# power-afe.net
KiCad netlist of a schematic drawn in Altium Designer
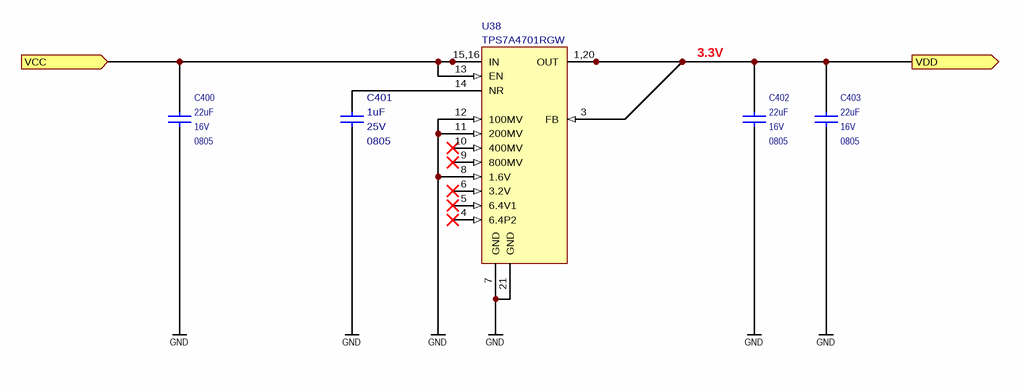
[diagram p0: power-afe.SchDoc]

(export (version "E")
  (design (tool "Eeschema 10.0.6"))
  (components
    (comp (ref "C400")
      (value "22uF")
      (footprint "generic:CAPC200X125X145L45N")
      (description "Ceramic Capacitor 22uF ±10% 16V X5R 0805")
      (fields
        (field (name "MANUFACTURER") "TDK")
        (field (name "VOLTAGE") "16V")
        (field (name "PACKAGE") "0805")
        (field (name "TOLERANCE") "±10%")
      )
      (libsource (lib "generic") (part "CAP 0603"))
    )
    (comp (ref "C401")
      (value "1uF")
      (footprint "CAPC200X125X145L45N")
      (description "Ceramic Capacitor 1uF ±10% 25V X7R 0805")
      (fields
        (field (name "MANUFACTURER") "Taiyo Yuden")
        (field (name "TOLERANCE") "±10%")
        (field (name "PACKAGE") "0805")
        (field (name "VOLTAGE") "25V")
      )
      (libsource (lib "capacitors") (part "CAP"))
    )
    (comp (ref "C402")
      (value "22uF")
      (footprint "generic:CAPC200X125X145L45N")
      (description "Ceramic Capacitor 22uF ±10% 16V X5R 0805")
      (fields
        (field (name "MANUFACTURER") "TDK")
        (field (name "VOLTAGE") "16V")
        (field (name "PACKAGE") "0805")
        (field (name "TOLERANCE") "±10%")
      )
      (libsource (lib "generic") (part "CAP 0603"))
    )
    (comp (ref "C403")
      (value "22uF")
      (footprint "generic:CAPC200X125X145L45N")
      (description "Ceramic Capacitor 22uF ±10% 16V X5R 0805")
      (fields
        (field (name "MANUFACTURER") "TDK")
        (field (name "VOLTAGE") "16V")
        (field (name "PACKAGE") "0805")
        (field (name "TOLERANCE") "±10%")
      )
      (libsource (lib "generic") (part "CAP 0603"))
    )
    (comp (ref "U38")
      (value "TPS7A4701RGW")
      (footprint "QFN65P500X500X100-21N")
      (description "Low-Dropout Linear Regulator 20-VQFN")
      (fields (field (name "MANUFACTURER") "Texas Instruments"))
      (libsource (lib "ti") (part "TPS7A4701RGW_1"))
    )
  )
  (nets
    (net (code "1") (name "/VCC") (class "Default")
      (node (ref "C400") (pin "2") (pinfunction "2_2") (pintype "passive"))
      (node (ref "U38") (pin "13") (pinfunction "EN_13") (pintype "input"))
      (node (ref "U38") (pin "15") (pinfunction "IN_15") (pintype "passive"))
      (node (ref "U38") (pin "16") (pinfunction "IN_16") (pintype "passive"))
    )
    (net (code "2") (name "/VDD") (class "Default")
      (node (ref "C402") (pin "2") (pinfunction "2_2") (pintype "passive"))
      (node (ref "C403") (pin "2") (pinfunction "2_2") (pintype "passive"))
      (node (ref "U38") (pin "1") (pinfunction "OUT_1") (pintype "passive"))
      (node (ref "U38") (pin "20") (pinfunction "OUT_20") (pintype "passive"))
      (node (ref "U38") (pin "3") (pinfunction "FB_3") (pintype "input"))
    )
    (net (code "3") (name "GND") (class "Default")
      (node (ref "C400") (pin "1") (pinfunction "1_1") (pintype "passive"))
      (node (ref "C401") (pin "2") (pinfunction "2_2") (pintype "passive"))
      (node (ref "C402") (pin "1") (pinfunction "1_1") (pintype "passive"))
      (node (ref "C403") (pin "1") (pinfunction "1_1") (pintype "passive"))
      (node (ref "U38") (pin "11") (pinfunction "200MV_11") (pintype "input"))
      (node (ref "U38") (pin "12") (pinfunction "100MV_12") (pintype "input"))
      (node (ref "U38") (pin "21") (pinfunction "GND_21") (pintype "power_in"))
      (node (ref "U38") (pin "7") (pinfunction "GND_7") (pintype "power_in"))
      (node (ref "U38") (pin "8") (pinfunction "1.6V_8") (pintype "input"))
    )
    (net (code "4") (name "Net-(U38-NR)") (class "Default")
      (node (ref "C401") (pin "1") (pinfunction "1_1") (pintype "passive"))
      (node (ref "U38") (pin "14") (pinfunction "NR_14") (pintype "passive"))
    )
    (net (code "5") (name "unconnected-(U38-3.2V-Pad6)") (class "Default")
      (node (ref "U38") (pin "6") (pinfunction "3.2V_6") (pintype "input+no_connect"))
    )
    (net (code "6") (name "unconnected-(U38-6.4P2-Pad4)") (class "Default")
      (node (ref "U38") (pin "4") (pinfunction "6.4P2_4") (pintype "input+no_connect"))
    )
    (net (code "7") (name "unconnected-(U38-6.4V1-Pad5)") (class "Default")
      (node (ref "U38") (pin "5") (pinfunction "6.4V1_5") (pintype "input+no_connect"))
    )
    (net (code "8") (name "unconnected-(U38-400MV-Pad10)") (class "Default")
      (node (ref "U38") (pin "10") (pinfunction "400MV_10") (pintype "input+no_connect"))
    )
    (net (code "9") (name "unconnected-(U38-800MV-Pad9)") (class "Default")
      (node (ref "U38") (pin "9") (pinfunction "800MV_9") (pintype "input+no_connect"))
    )
  )
)
